# USB___Power.net
KiCad netlist of a schematic drawn in Altium Designer
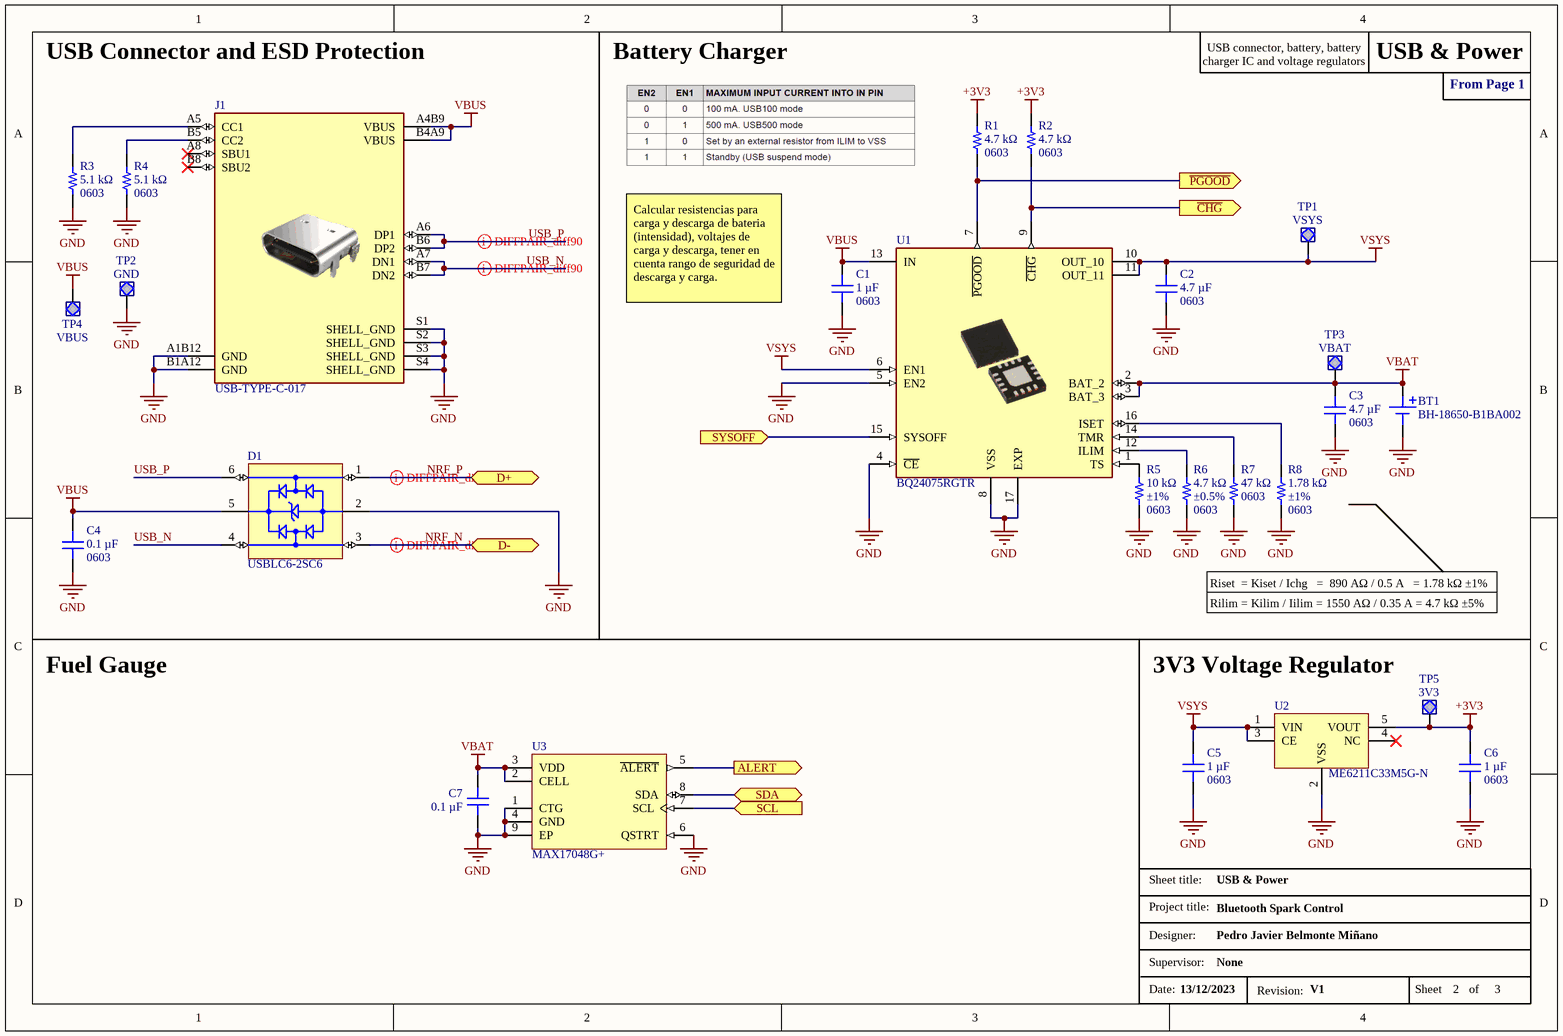
[diagram p0: USB_&_Power.SchDoc]

(export (version "E")
  (design (tool "Eeschema 10.0.6"))
  (components
    (comp (ref "BT1")
      (value "BH-18650-B1BA002")
      (footprint "BH-18650-B1BA002")
      (fields (field (name "MF") "MPD _Memory") (field (name "MP") "BH-18650-PC"))
      (libsource (lib "SparkControl") (part "BH-18650-B1BA002"))
    )
    (comp (ref "C1")
      (value "1 µF")
      (footprint "CAP 0603_1608")
      (description "CAP CER 1UF 25V X7R 0603")
      (fields
        (field (name "PART NUMBER") "0603B105K250CT")
        (field (name "DEVICE PACKAGE") "0603")
        (field (name "MANUFACTURER") "Walsin Technology Corporation")
      )
      (libsource (lib "SparkControl") (part "0603B105K250CT"))
    )
    (comp (ref "C2")
      (value "4.7 µF")
      (footprint "CAP 0603_1608")
      (description "CAP CER 4.7UF 16V X6S 0603")
      (fields
        (field (name "PART NUMBER") "0603YW475KAT2A")
        (field (name "DEVICE PACKAGE") "0603")
        (field (name "MANUFACTURER") "KYOCERA AVX")
      )
      (libsource (lib "SparkControl") (part "0603YW475KAT2A"))
    )
    (comp (ref "C3")
      (value "4.7 µF")
      (footprint "CAP 0603_1608")
      (description "CAP CER 4.7UF 16V X6S 0603")
      (fields
        (field (name "PART NUMBER") "0603YW475KAT2A")
        (field (name "DEVICE PACKAGE") "0603")
        (field (name "MANUFACTURER") "KYOCERA AVX")
      )
      (libsource (lib "SparkControl") (part "0603YW475KAT2A"))
    )
    (comp (ref "C4")
      (value "0.1 µF")
      (footprint "CAP 0603_1608")
      (description "CAP CER 0.1UF 10V X7R 0603")
      (fields
        (field (name "PART NUMBER") "100X14W104MV4T")
        (field (name "DEVICE PACKAGE") "0603")
        (field (name "MANUFACTURER") "Johanson Dielectrics Inc.")
      )
      (libsource (lib "SparkControl") (part "100X14W104MV4T"))
    )
    (comp (ref "C5")
      (value "1 µF")
      (footprint "CAP 0603_1608")
      (description "CAP CER 1UF 25V X7R 0603")
      (fields
        (field (name "PART NUMBER") "0603B105K250CT")
        (field (name "DEVICE PACKAGE") "0603")
        (field (name "MANUFACTURER") "Walsin Technology Corporation")
      )
      (libsource (lib "SparkControl") (part "0603B105K250CT"))
    )
    (comp (ref "C6")
      (value "1 µF")
      (footprint "CAP 0603_1608")
      (description "CAP CER 1UF 25V X7R 0603")
      (fields
        (field (name "PART NUMBER") "0603B105K250CT")
        (field (name "DEVICE PACKAGE") "0603")
        (field (name "MANUFACTURER") "Walsin Technology Corporation")
      )
      (libsource (lib "SparkControl") (part "0603B105K250CT"))
    )
    (comp (ref "C7")
      (value "0.1 µF")
      (footprint "CAP 0603_1608")
      (description "CAP CER 0.1UF 50V X7R 0603")
      (fields (field (name "PART NUMBER") "C0603C104K5RAC7411") (field (name "MANUFACTURER") "KEMET"))
      (libsource (lib "SparkControl") (part "C0603C104K5RAC7411"))
    )
    (comp (ref "D1")
      (value "USBLC6-2SC6")
      (footprint "SOT95P280X145-6N")
      (description "Very low capacitance ESD protection, 3.5 pF, -40 to 125 degC, 6-Pin SOT23, RoHS, Tape and Reel")
      (fields (field (name "MANUFACTURER") "STMicroelectronics"))
      (libsource (lib "SparkControl") (part "USBLC6-2SC6"))
    )
    (comp (ref "J1")
      (value "USB-TYPE-C-017")
      (footprint "USB-TYPE-C-017")
      (description "3A 1 Surface Mount 16P Female -25℃~+85℃ Type-C SMD USB Connectors ROHS")
      (fields (field (name "MF") "Valcon") (field (name "MP") "CSP-USC16-TR"))
      (libsource (lib "SparkControl") (part "USB-TYPE-C-017"))
    )
    (comp (ref "R1")
      (value "4.7 kΩ")
      (footprint "RES 0603_1608")
      (description "RES SMD 4.7K OHM 0.1% 1/10W 0603")
      (fields
        (field (name "PART NUMBER") "ERA-3AEB472V")
        (field (name "DEVICE PACKAGE") "0603")
        (field (name "MANUFACTURER") "Panasonic Electronic Components")
      )
      (libsource (lib "SparkControl") (part "ERA-3AEB472V"))
    )
    (comp (ref "R2")
      (value "4.7 kΩ")
      (footprint "RES 0603_1608")
      (description "RES SMD 4.7K OHM 0.1% 1/10W 0603")
      (fields
        (field (name "PART NUMBER") "ERA-3AEB472V")
        (field (name "DEVICE PACKAGE") "0603")
        (field (name "MANUFACTURER") "Panasonic Electronic Components")
      )
      (libsource (lib "SparkControl") (part "ERA-3AEB472V"))
    )
    (comp (ref "R3")
      (value "5.1 kΩ")
      (footprint "RES 0603_1608")
      (description "RES 5.1K OHM 5% 1/10W 0603")
      (fields
        (field (name "PART NUMBER") "RMCF0603JG5K10")
        (field (name "DEVICE PACKAGE") "0603")
        (field (name "MANUFACTURER") "Stackpole Electronics Inc")
      )
      (libsource (lib "SparkControl") (part "RMCF0603JG5K10"))
    )
    (comp (ref "R4")
      (value "5.1 kΩ")
      (footprint "RES 0603_1608")
      (description "RES 5.1K OHM 5% 1/10W 0603")
      (fields
        (field (name "PART NUMBER") "RMCF0603JG5K10")
        (field (name "DEVICE PACKAGE") "0603")
        (field (name "MANUFACTURER") "Stackpole Electronics Inc")
      )
      (libsource (lib "SparkControl") (part "RMCF0603JG5K10"))
    )
    (comp (ref "R5")
      (value "10 kΩ")
      (footprint "RES 0603_1608")
      (description "RES SMD 10K OHM 1% 1/10W 0603")
      (fields
        (field (name "PART NUMBER") "RT0603FRE0710KL")
        (field (name "DEVICE PACKAGE") "0603")
        (field (name "MANUFACTURER") "Yageo")
        (field (name "TOLERANCE") "±1%")
      )
      (libsource (lib "SparkControl") (part "RT0603FRE0710KL"))
    )
    (comp (ref "R6")
      (value "4.7 kΩ")
      (footprint "RES 0603_1608")
      (description "RES SMD 4.7K OHM 0.1% 1/10W 0603")
      (fields
        (field (name "PART NUMBER") "ERA-3AEB472V")
        (field (name "DEVICE PACKAGE") "0603")
        (field (name "MANUFACTURER") "Panasonic Electronic Components")
        (field (name "TOLERANCE") "±0.5%")
      )
      (libsource (lib "SparkControl") (part "ERA-3AEB472V"))
    )
    (comp (ref "R7")
      (value "47 kΩ")
      (footprint "RES 0603_1608")
      (description "RES SMD 47K OHM 5% 1/4W 0603")
      (fields
        (field (name "PART NUMBER") "RCS060347K0JNEA")
        (field (name "DEVICE PACKAGE") "0603")
        (field (name "MANUFACTURER") "Vishay Dale")
      )
      (libsource (lib "SparkControl") (part "RCS060347K0JNEA"))
    )
    (comp (ref "R8")
      (value "1.78 kΩ")
      (footprint "RES 0603_1608")
      (description "RES 1.78K OHM 1% 1/8W 0603")
      (fields
        (field (name "PART NUMBER") "RNCP0603FTD1K78")
        (field (name "DEVICE PACKAGE") "0603")
        (field (name "MANUFACTURER") "Stackpole Electronics Inc")
        (field (name "TOLERANCE") "±1%")
      )
      (libsource (lib "SparkControl") (part "RNCP0603FTD1K78"))
    )
    (comp (ref "TP1")
      (value "VSYS")
      (footprint "TestPoint")
      (description "TestPoint")
      (libsource (lib "SparkControl") (part "TestPoint"))
    )
    (comp (ref "TP2")
      (value "GND")
      (footprint "TestPoint")
      (description "TestPoint")
      (libsource (lib "SparkControl") (part "TestPoint"))
    )
    (comp (ref "TP3")
      (value "VBAT")
      (footprint "TestPoint")
      (description "TestPoint")
      (libsource (lib "SparkControl") (part "TestPoint"))
    )
    (comp (ref "TP4")
      (value "VBUS")
      (footprint "TestPoint")
      (description "TestPoint")
      (libsource (lib "SparkControl") (part "TestPoint"))
    )
    (comp (ref "TP5")
      (value "3V3")
      (footprint "TestPoint")
      (description "TestPoint")
      (libsource (lib "SparkControl") (part "TestPoint"))
    )
    (comp (ref "U1")
      (value "BQ24075RGTR")
      (footprint "QFN50P300X300X100-17N")
      (description "Standalone 1-cell 1.5-A linear charger, Power Path, 4.2-V VBAT and 5.5-V VOUT 16-VQFN -40 to 85")
      (libsource (lib "SparkControl") (part "BQ24075RGTR"))
    )
    (comp (ref "U2")
      (value "ME6211C33M5G-N")
      (footprint "SOT95P270X145-5N")
      (description "Fixed 6V 3.3V 500mA SOT-23-5 Low Dropout Regulators(LDO) RoHS")
      (libsource (lib "SparkControl") (part "ME6211C33M5G-N"))
    )
    (comp (ref "U3")
      (value "MAX17048G+")
      (footprint "SON50P200X200X80-9N")
      (description "Battery Battery Monitor IC Lithium-Ion 8-TDFN-EP _2x2_")
      (fields (field (name "MF") "Maxim Integrated"))
      (libsource (lib "SparkControl") (part "MAX17048G+"))
    )
  )
  (nets
    (net (code "1") (name "+3V3") (class "Default")
      (node (ref "C6") (pin "2") (pinfunction "2_2") (pintype "passive"))
      (node (ref "R1") (pin "2") (pinfunction "2_2") (pintype "passive"))
      (node (ref "R2") (pin "2") (pinfunction "2_2") (pintype "passive"))
      (node (ref "TP5") (pin "1") (pinfunction "1_1") (pintype "passive"))
      (node (ref "U2") (pin "5") (pinfunction "VOUT_5") (pintype "passive"))
    )
    (net (code "2") (name "/ALERT") (class "Default")
      (node (ref "U3") (pin "5") (pinfunction "~{ALERT}_5") (pintype "output"))
    )
    (net (code "3") (name "/NRF_N") (class "Default")
      (node (ref "D1") (pin "3") (pinfunction "I/O_2_3") (pintype "bidirectional"))
    )
    (net (code "4") (name "/NRF_P") (class "Default")
      (node (ref "D1") (pin "1") (pinfunction "I/O_1_1") (pintype "bidirectional"))
    )
    (net (code "5") (name "/SCL") (class "Default")
      (node (ref "U3") (pin "7") (pinfunction "SCL_7") (pintype "input"))
    )
    (net (code "6") (name "/SDA") (class "Default")
      (node (ref "U3") (pin "8") (pinfunction "SDA_8") (pintype "bidirectional"))
    )
    (net (code "7") (name "/SYSOFF") (class "Default")
      (node (ref "U1") (pin "15") (pinfunction "SYSOFF_15") (pintype "input"))
    )
    (net (code "8") (name "/USB_N") (class "Default")
      (node (ref "D1") (pin "4") (pinfunction "I/O_3_4") (pintype "bidirectional"))
      (node (ref "J1") (pin "A7") (pinfunction "DN1_A7") (pintype "bidirectional"))
      (node (ref "J1") (pin "B7") (pinfunction "DN2_B7") (pintype "bidirectional"))
    )
    (net (code "9") (name "/USB_P") (class "Default")
      (node (ref "D1") (pin "6") (pinfunction "I/O_4_6") (pintype "bidirectional"))
      (node (ref "J1") (pin "A6") (pinfunction "DP1_A6") (pintype "bidirectional"))
      (node (ref "J1") (pin "B6") (pinfunction "DP2_B6") (pintype "bidirectional"))
    )
    (net (code "10") (name "/~{CHG}") (class "Default")
      (node (ref "R2") (pin "1") (pinfunction "1_1") (pintype "passive"))
      (node (ref "U1") (pin "9") (pinfunction "~{CHG}_9") (pintype "output"))
    )
    (net (code "11") (name "/~{PGOOD}") (class "Default")
      (node (ref "R1") (pin "1") (pinfunction "1_1") (pintype "passive"))
      (node (ref "U1") (pin "7") (pinfunction "~{PGOOD}_7") (pintype "output"))
    )
    (net (code "12") (name "GND") (class "Default")
      (node (ref "BT1") (pin "N") (pinfunction "NEG_N") (pintype "passive"))
      (node (ref "C1") (pin "1") (pinfunction "1_1") (pintype "passive"))
      (node (ref "C2") (pin "1") (pinfunction "1_1") (pintype "passive"))
      (node (ref "C3") (pin "1") (pinfunction "1_1") (pintype "passive"))
      (node (ref "C4") (pin "1") (pinfunction "1_1") (pintype "passive"))
      (node (ref "C5") (pin "1") (pinfunction "1_1") (pintype "passive"))
      (node (ref "C6") (pin "1") (pinfunction "1_1") (pintype "passive"))
      (node (ref "C7") (pin "1") (pinfunction "1_1") (pintype "passive"))
      (node (ref "D1") (pin "2") (pinfunction "GND_2") (pintype "passive"))
      (node (ref "J1") (pin "A1B12") (pinfunction "GND_A1B12") (pintype "power_in"))
      (node (ref "J1") (pin "B1A12") (pinfunction "GND_B1A12") (pintype "power_in"))
      (node (ref "J1") (pin "S1") (pinfunction "SHELL_GND_S1") (pintype "power_in"))
      (node (ref "J1") (pin "S2") (pinfunction "SHELL_GND_S2") (pintype "power_in"))
      (node (ref "J1") (pin "S3") (pinfunction "SHELL_GND_S3") (pintype "power_in"))
      (node (ref "J1") (pin "S4") (pinfunction "SHELL_GND_S4") (pintype "power_in"))
      (node (ref "R3") (pin "1") (pinfunction "1_1") (pintype "passive"))
      (node (ref "R4") (pin "1") (pinfunction "1_1") (pintype "passive"))
      (node (ref "R5") (pin "1") (pinfunction "1_1") (pintype "passive"))
      (node (ref "R6") (pin "1") (pinfunction "1_1") (pintype "passive"))
      (node (ref "R7") (pin "1") (pinfunction "1_1") (pintype "passive"))
      (node (ref "R8") (pin "1") (pinfunction "1_1") (pintype "passive"))
      (node (ref "TP2") (pin "1") (pinfunction "1_1") (pintype "passive"))
      (node (ref "U1") (pin "17") (pinfunction "EXP_17") (pintype "power_in"))
      (node (ref "U1") (pin "4") (pinfunction "~{CE}_4") (pintype "input"))
      (node (ref "U1") (pin "5") (pinfunction "EN2_5") (pintype "input"))
      (node (ref "U1") (pin "8") (pinfunction "VSS_8") (pintype "power_in"))
      (node (ref "U2") (pin "2") (pinfunction "VSS_2") (pintype "passive"))
      (node (ref "U3") (pin "1") (pinfunction "CTG_1") (pintype "power_in"))
      (node (ref "U3") (pin "4") (pinfunction "GND_4") (pintype "power_in"))
      (node (ref "U3") (pin "6") (pinfunction "QSTRT_6") (pintype "input"))
      (node (ref "U3") (pin "9") (pinfunction "EP_9") (pintype "power_in"))
    )
    (net (code "13") (name "Net-(J1-CC1)") (class "Default")
      (node (ref "J1") (pin "A5") (pinfunction "CC1_A5") (pintype "bidirectional"))
      (node (ref "R3") (pin "2") (pinfunction "2_2") (pintype "passive"))
    )
    (net (code "14") (name "Net-(J1-CC2)") (class "Default")
      (node (ref "J1") (pin "B5") (pinfunction "CC2_B5") (pintype "bidirectional"))
      (node (ref "R4") (pin "2") (pinfunction "2_2") (pintype "passive"))
    )
    (net (code "15") (name "Net-(U1-ILIM)") (class "Default")
      (node (ref "R6") (pin "2") (pinfunction "2_2") (pintype "passive"))
      (node (ref "U1") (pin "12") (pinfunction "ILIM_12") (pintype "input"))
    )
    (net (code "16") (name "Net-(U1-ISET)") (class "Default")
      (node (ref "R8") (pin "2") (pinfunction "2_2") (pintype "passive"))
      (node (ref "U1") (pin "16") (pinfunction "ISET_16") (pintype "bidirectional"))
    )
    (net (code "17") (name "Net-(U1-TMR)") (class "Default")
      (node (ref "R7") (pin "2") (pinfunction "2_2") (pintype "passive"))
      (node (ref "U1") (pin "14") (pinfunction "TMR_14") (pintype "input"))
    )
    (net (code "18") (name "Net-(U1-TS)") (class "Default")
      (node (ref "R5") (pin "2") (pinfunction "2_2") (pintype "passive"))
      (node (ref "U1") (pin "1") (pinfunction "TS_1") (pintype "input"))
    )
    (net (code "19") (name "VBAT") (class "Default")
      (node (ref "BT1") (pin "P") (pinfunction "POS_P") (pintype "passive"))
      (node (ref "C3") (pin "2") (pinfunction "2_2") (pintype "passive"))
      (node (ref "C7") (pin "2") (pinfunction "2_2") (pintype "passive"))
      (node (ref "TP3") (pin "1") (pinfunction "1_1") (pintype "passive"))
      (node (ref "U1") (pin "2") (pinfunction "BAT_2_2") (pintype "bidirectional"))
      (node (ref "U1") (pin "3") (pinfunction "BAT_3_3") (pintype "bidirectional"))
      (node (ref "U3") (pin "2") (pinfunction "CELL_2") (pintype "power_in"))
      (node (ref "U3") (pin "3") (pinfunction "VDD_3") (pintype "power_in"))
    )
    (net (code "20") (name "VBUS") (class "Default")
      (node (ref "C1") (pin "2") (pinfunction "2_2") (pintype "passive"))
      (node (ref "C4") (pin "2") (pinfunction "2_2") (pintype "passive"))
      (node (ref "D1") (pin "5") (pinfunction "VBUS_5") (pintype "passive"))
      (node (ref "J1") (pin "A4B9") (pinfunction "VBUS_A4B9") (pintype "power_in"))
      (node (ref "J1") (pin "B4A9") (pinfunction "VBUS_B4A9") (pintype "power_in"))
      (node (ref "TP4") (pin "1") (pinfunction "1_1") (pintype "passive"))
      (node (ref "U1") (pin "13") (pinfunction "IN_13") (pintype "power_in"))
    )
    (net (code "21") (name "VSYS") (class "Default")
      (node (ref "C2") (pin "2") (pinfunction "2_2") (pintype "passive"))
      (node (ref "C5") (pin "2") (pinfunction "2_2") (pintype "passive"))
      (node (ref "TP1") (pin "1") (pinfunction "1_1") (pintype "passive"))
      (node (ref "U1") (pin "10") (pinfunction "OUT_10_10") (pintype "power_in"))
      (node (ref "U1") (pin "11") (pinfunction "OUT_11_11") (pintype "power_in"))
      (node (ref "U1") (pin "6") (pinfunction "EN1_6") (pintype "input"))
      (node (ref "U2") (pin "1") (pinfunction "VIN_1") (pintype "passive"))
      (node (ref "U2") (pin "3") (pinfunction "CE_3") (pintype "passive"))
    )
    (net (code "22") (name "unconnected-(J1-SBU1-PadA8)") (class "Default")
      (node (ref "J1") (pin "A8") (pinfunction "SBU1_A8") (pintype "bidirectional+no_connect"))
    )
    (net (code "23") (name "unconnected-(J1-SBU2-PadB8)") (class "Default")
      (node (ref "J1") (pin "B8") (pinfunction "SBU2_B8") (pintype "bidirectional+no_connect"))
    )
    (net (code "24") (name "unconnected-(U2-NC-Pad4)") (class "Default")
      (node (ref "U2") (pin "4") (pinfunction "NC_4") (pintype "passive+no_connect"))
    )
  )
)
